# EasySerial.net
KiCad netlist of a schematic drawn in Altium Designer
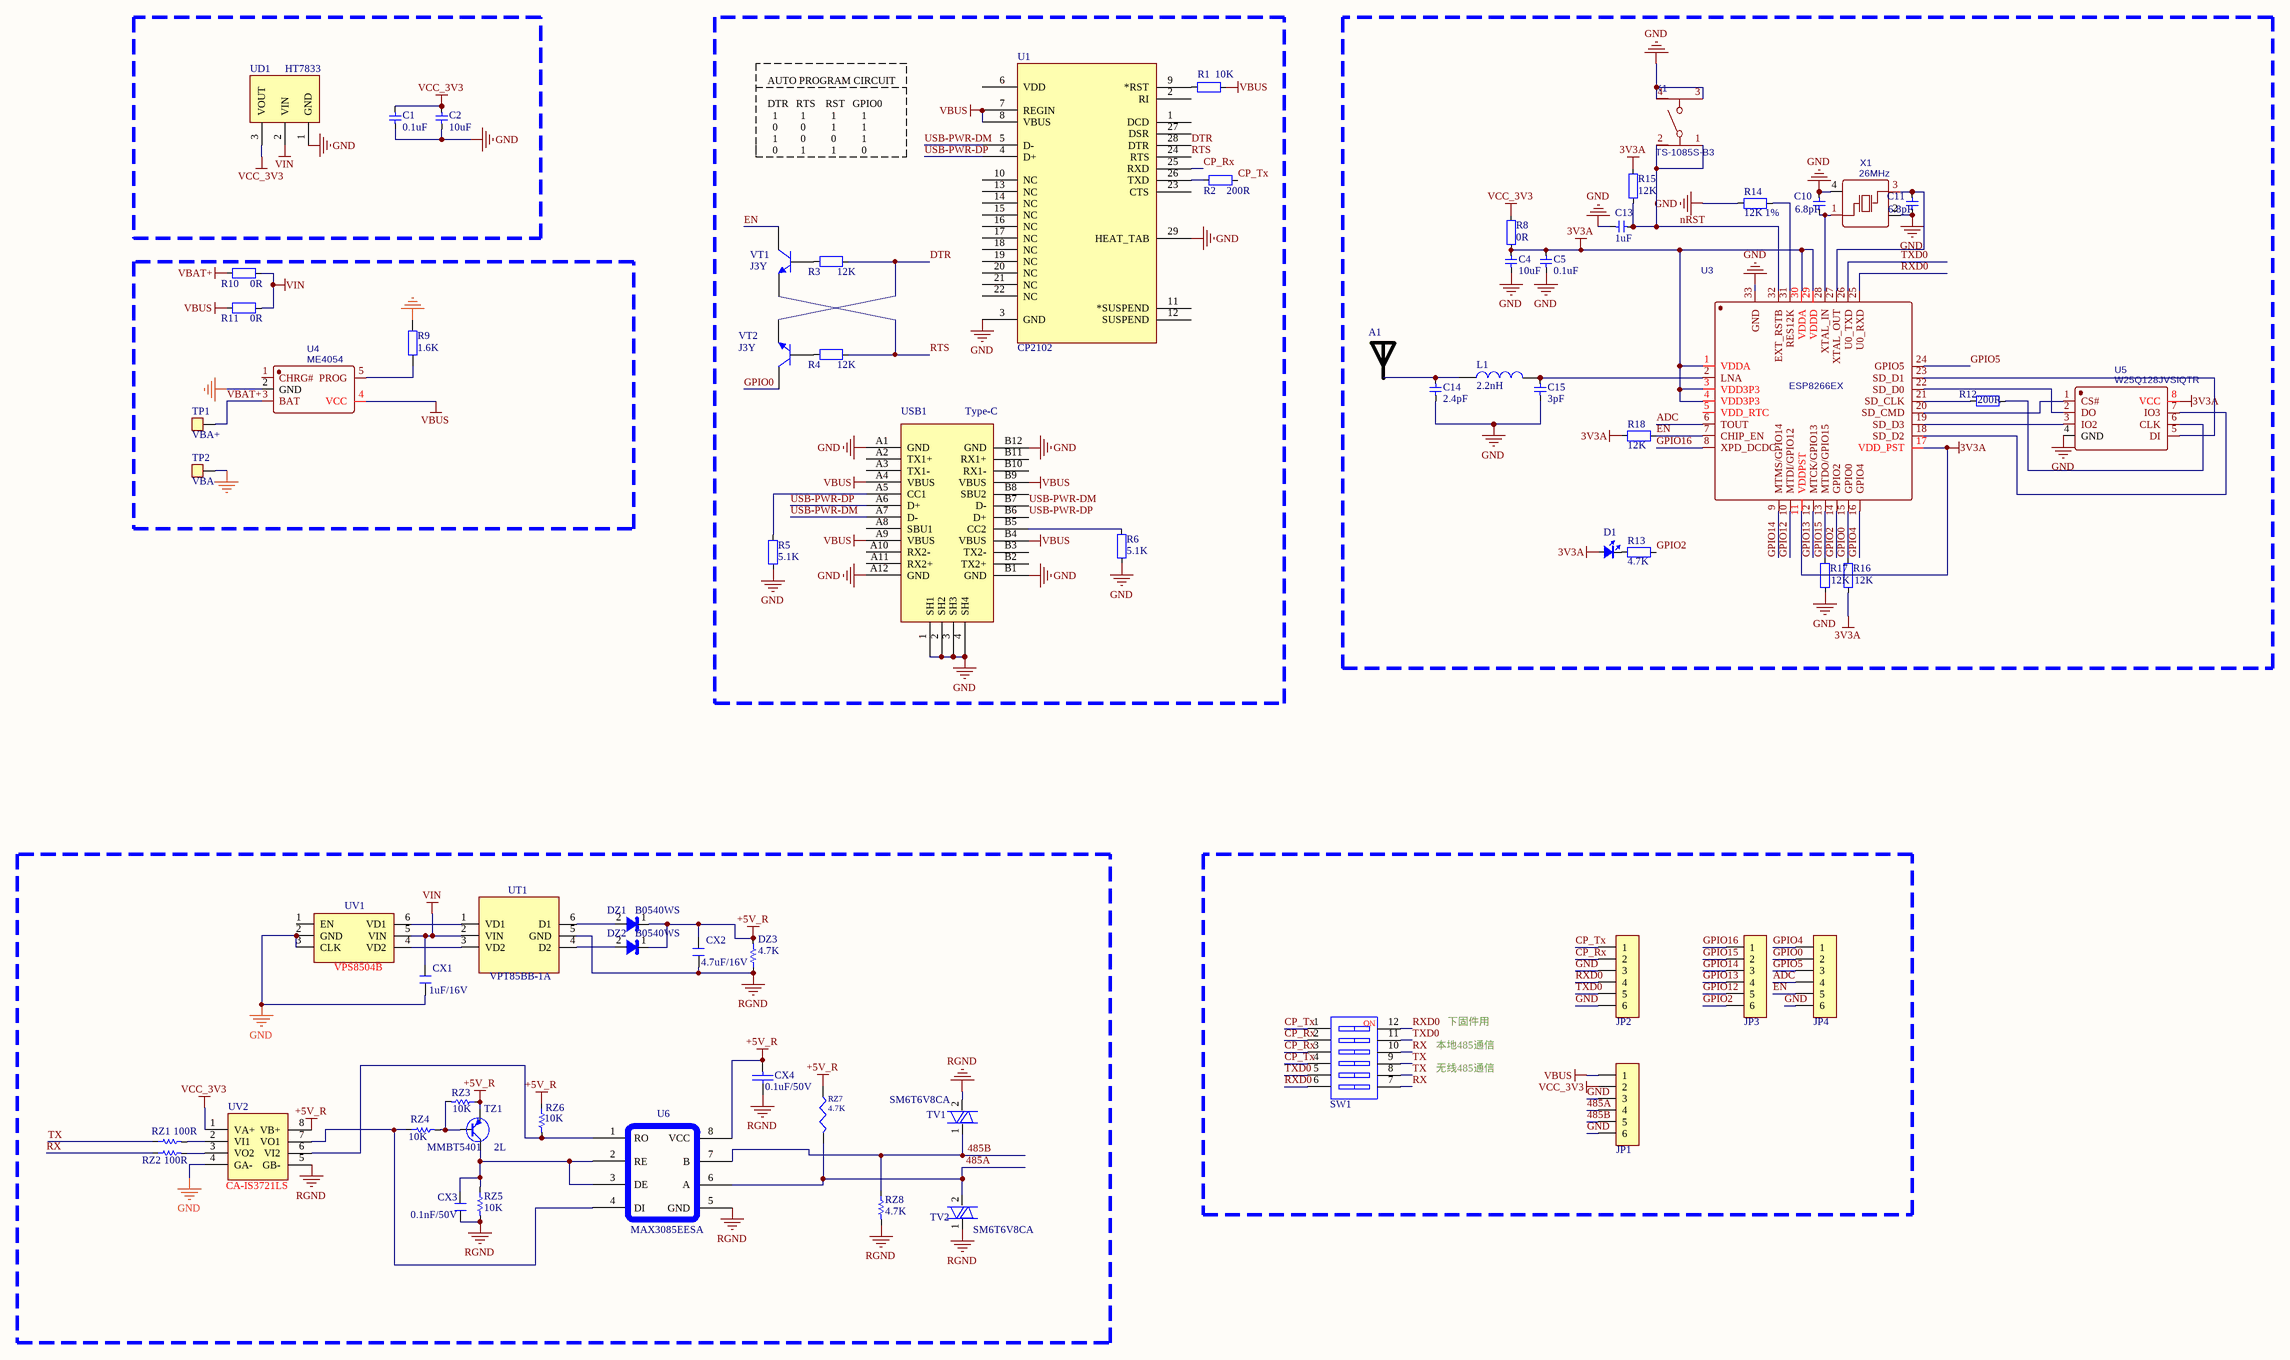
[diagram p0: EasySerial.SchDoc]

(export (version "E")
  (design (tool "Eeschema 10.0.6"))
  (components
    (comp (ref "A1")
      (value "RAINSUN")
      (footprint "ANT-Rainsun-AN5120")
      (libsource (lib "MyPcbLib") (part "ANT-Rainsun-AP5120"))
    )
    (comp (ref "C1")
      (value "0.1uF")
      (footprint "C 0402")
      (description "Capacitor")
      (libsource (lib "MyPcbLib") (part "电容-0402"))
    )
    (comp (ref "C2")
      (value "10uF")
      (footprint "C 0402")
      (description "Capacitor")
      (libsource (lib "MyPcbLib") (part "电容-0402"))
    )
    (comp (ref "C4")
      (value "10uF")
      (footprint "C 0402")
      (description "Capacitor")
      (libsource (lib "MyPcbLib") (part "电容-0402"))
    )
    (comp (ref "C5")
      (value "0.1uF")
      (footprint "C 0402")
      (description "Capacitor")
      (libsource (lib "MyPcbLib") (part "电容-0402"))
    )
    (comp (ref "C10")
      (value "6.8pF")
      (footprint "C 0402")
      (description "Capacitor")
      (libsource (lib "MyPcbLib") (part "电容-0402"))
    )
    (comp (ref "C11")
      (value "6.8pF")
      (footprint "C 0402")
      (description "Capacitor")
      (libsource (lib "MyPcbLib") (part "电容-0402"))
    )
    (comp (ref "C13")
      (value "1uF")
      (footprint "C 0402")
      (description "Capacitor")
      (libsource (lib "MyPcbLib") (part "电容-0402"))
    )
    (comp (ref "C14")
      (value "2.4pF")
      (footprint "C 0402")
      (description "Capacitor")
      (libsource (lib "MyPcbLib") (part "电容-0402"))
    )
    (comp (ref "C15")
      (value "3pF")
      (footprint "C 0402")
      (description "Capacitor")
      (libsource (lib "MyPcbLib") (part "电容-0402"))
    )
    (comp (ref "CX1") (value "1uF/16V") (footprint "C 0402") (libsource (lib "DaWei") (part "CAP")))
    (comp (ref "CX2") (value "4.7uF/16V") (footprint "C 0402") (libsource (lib "DaWei") (part "CAP")))
    (comp (ref "CX3") (value "0.1nF/50V") (footprint "C 0402") (libsource (lib "DaWei") (part "CAP")))
    (comp (ref "CX4")
      (value "0.1uF/50V")
      (footprint "C 0402")
      (description "Capacitor")
      (libsource (lib "*") (part "CAP"))
    )
    (comp (ref "D1")
      (value "color?")
      (footprint "LED_0402_RED")
      (description "LED")
      (libsource (lib "ESP32-PicoDK") (part "LED_0402"))
    )
    (comp (ref "DZ1") (value "B0540WS") (footprint "SOD-323F") (libsource (lib "DaWei") (part "DIODE")))
    (comp (ref "DZ2") (value "B0540WS") (footprint "SOD-323F") (libsource (lib "DaWei") (part "DIODE")))
    (comp (ref "DZ3") (value "4.7K") (footprint "R 0402") (libsource (lib "DaWei") (part "R-SMD")))
    (comp (ref "JP1")
      (value "HDR-1X6")
      (footprint "HDR2.54 S-W-6P")
      (description "6P接插件")
      (fields (field (name "版权归属") "源创客"))
      (libsource (lib "接插件") (part "Header 6"))
    )
    (comp (ref "JP2")
      (value "HDR-1X6")
      (footprint "HDR2.54 S-W-6P")
      (description "6P接插件")
      (fields (field (name "版权归属") "源创客"))
      (libsource (lib "接插件") (part "Header 6"))
    )
    (comp (ref "JP3")
      (value "HDR-1X6")
      (footprint "HDR-1X6")
      (description "6P接插件")
      (fields (field (name "版权归属") "源创客"))
      (libsource (lib "接插件") (part "Header 6"))
    )
    (comp (ref "JP4")
      (value "HDR-1X6")
      (footprint "HDR-1X6")
      (description "6P接插件")
      (fields (field (name "版权归属") "源创客"))
      (libsource (lib "接插件") (part "Header 6"))
    )
    (comp (ref "K1")
      (value "TS-1085S-B3")
      (footprint "TS-1085S-B3")
      (fields (field (name "BOM_SUPPLIER PART") "C498298") (field (name "CONTRIBUTOR") "LCSC"))
      (libsource (lib "altium-import") (part "root_2_TS-1085S-B3_"))
    )
    (comp (ref "L1")
      (value "2.2nH")
      (footprint "L 0402")
      (description "小功率贴片电感")
      (fields (field (name "版权归属") "源创客"))
      (libsource (lib "电阻-电容-电感") (part "L"))
    )
    (comp (ref "R1")
      (value "10K")
      (footprint "R 0402")
      (description "Resistor")
      (libsource (lib "") (part "电阻-0402_3"))
    )
    (comp (ref "R2")
      (value "200R")
      (footprint "R 0402")
      (description "Resistor")
      (libsource (lib "") (part "电阻-0402_3"))
    )
    (comp (ref "R3")
      (value "12K")
      (footprint "R 0402")
      (description "Resistor")
      (libsource (lib "") (part "电阻-0402_3"))
    )
    (comp (ref "R4")
      (value "12K")
      (footprint "R 0402")
      (description "Resistor")
      (libsource (lib "") (part "电阻-0402_3"))
    )
    (comp (ref "R5")
      (value "5.1K")
      (footprint "R 0402")
      (description "Resistor")
      (libsource (lib "") (part "电阻-0402_1"))
    )
    (comp (ref "R6")
      (value "5.1K")
      (footprint "R 0402")
      (description "Resistor")
      (libsource (lib "") (part "电阻-0402_1"))
    )
    (comp (ref "R8")
      (value "0R")
      (footprint "R 0402")
      (description "Resistor")
      (libsource (lib "") (part "电阻-0402_1"))
    )
    (comp (ref "R9")
      (value "1.6K")
      (footprint "R 0603")
      (description "Resistor")
      (fields (field (name "PUBLISHER") "Altium Limited"))
      (libsource (lib "Miscellaneous Devices") (part "Res2"))
    )
    (comp (ref "R10")
      (value "0R")
      (footprint "R 0603")
      (description "Resistor")
      (libsource (lib "") (part "电阻-0402_3"))
    )
    (comp (ref "R11")
      (value "0R")
      (footprint "R 0603")
      (description "Resistor")
      (libsource (lib "") (part "电阻-0402_3"))
    )
    (comp (ref "R12")
      (value "200R")
      (footprint "R 0402")
      (description "Resistor")
      (libsource (lib "") (part "电阻-0402_2"))
    )
    (comp (ref "R13")
      (value "4.7K")
      (footprint "R 0402")
      (description "Resistor")
      (libsource (lib "") (part "电阻-0402_2"))
    )
    (comp (ref "R14")
      (value "12K 1%")
      (footprint "R 0402")
      (description "Resistor")
      (libsource (lib "") (part "电阻-0402_2"))
    )
    (comp (ref "R15")
      (value "12K")
      (footprint "R 0402")
      (description "Resistor")
      (libsource (lib "MyPcbLib") (part "电阻-0402"))
    )
    (comp (ref "R16")
      (value "12K")
      (footprint "R 0402")
      (description "Resistor")
      (libsource (lib "MyPcbLib") (part "电阻-0402"))
    )
    (comp (ref "R17")
      (value "12K")
      (footprint "R 0402")
      (description "Resistor")
      (libsource (lib "MyPcbLib") (part "电阻-0402"))
    )
    (comp (ref "R18")
      (value "12K")
      (footprint "R 0402")
      (description "Resistor")
      (libsource (lib "") (part "电阻-0402_3"))
    )
    (comp (ref "RZ1") (value "100R") (footprint "R 0402") (libsource (lib "DaWei") (part "R-SMD")))
    (comp (ref "RZ2") (value "100R") (footprint "R 0402") (libsource (lib "DaWei") (part "R-SMD")))
    (comp (ref "RZ3") (value "10K") (footprint "R 0402") (libsource (lib "DaWei") (part "R-SMD")))
    (comp (ref "RZ4") (value "10K") (footprint "R 0402") (libsource (lib "DaWei") (part "R-SMD")))
    (comp (ref "RZ5") (value "10K") (footprint "R 0402") (libsource (lib "DaWei") (part "R-SMD")))
    (comp (ref "RZ6") (value "10K") (footprint "R 0402") (libsource (lib "DaWei") (part "R-SMD")))
    (comp (ref "RZ7") (value "4.7K") (footprint "R 0402") (libsource (lib "*") (part "RES1")))
    (comp (ref "RZ8") (value "4.7K") (footprint "R 0402") (libsource (lib "DaWei") (part "R-SMD")))
    (comp (ref "SW1")
      (value "CSW-6P")
      (footprint "CSW1.27 SMD-6P")
      (description "6路编码开关")
      (fields (field (name "版权归属") "源创客"))
      (libsource (lib "按键-开关") (part "CSW-6P"))
    )
    (comp (ref "TP1")
      (value "VBA+")
      (footprint "TEST 1.8")
      (description "测试点")
      (fields (field (name "版权归属") "源创客"))
      (libsource (lib "未分类器件") (part "TEST_D"))
    )
    (comp (ref "TP2")
      (value "VBA-")
      (footprint "TEST 1.8")
      (description "测试点")
      (fields (field (name "版权归属") "源创客"))
      (libsource (lib "未分类器件") (part "TEST_D"))
    )
    (comp (ref "TV1") (value "SM6T6V8CA") (footprint "SMB") (libsource (lib "*") (part "ZD1")))
    (comp (ref "TV2") (value "SM6T6V8CA") (footprint "SMB") (libsource (lib "*") (part "ZD1")))
    (comp (ref "TZ1")
      (value "MMBT5401     2L")
      (footprint "SOT23-3N")
      (libsource (lib "DaWei") (part "PNP_R"))
    )
    (comp (ref "U1")
      (value "CP2102")
      (footprint "QFN-28")
      (description "USB转TTL")
      (libsource (lib "mLib") (part "CP2102"))
    )
    (comp (ref "U3")
      (value "ESP8266EX")
      (footprint "QFN32 5x5_L")
      (fields (field (name "BOM_SUPPLIER PART") "C77967"))
      (libsource (lib "altium-import") (part "root_0_ESP8266EX_"))
    )
    (comp (ref "U4")
      (value "ME4054")
      (footprint "SOT23-5L")
      (fields
        (field (name "BOM_SUPPLIER PART") "C521413")
        (field (name "BOM_MANUFACTURER PART") "SD8054")
        (field (name "CONTRIBUTOR") "LCSC")
      )
      (libsource (lib "altium-import") (part "root_0_SD8054_"))
    )
    (comp (ref "U5")
      (value "W25Q128JVSIQTR")
      (footprint "SOP8W_L")
      (fields (field (name "BOM_SUPPLIER PART") "C97521"))
      (libsource (lib "altium-import") (part "root_0_W25Q128JVSIQTR_"))
    )
    (comp (ref "U6") (value "MAX3085EESA") (footprint "SOP8_M") (libsource (lib "*") (part "MAX485")))
    (comp (ref "UD1")
      (value "HT7833")
      (footprint "SOT89_N")
      (description "LDO")
      (libsource (lib "DaWei") (part "HT75XX"))
    )
    (comp (ref "USB1")
      (value "Type-C")
      (footprint "Type-C")
      (libsource (lib "MyPcbLib") (part "USB-Type-C-TOP"))
    )
    (comp (ref "UT1")
      (value "VPT85BB-1A")
      (footprint "VPT85BB-1A")
      (description "源特推挽变压器")
      (libsource (lib "DaWei") (part "T-SMD"))
    )
    (comp (ref "UV1")
      (value "VPS8504B")
      (footprint "SOT23-6N")
      (description "源特微功率隔离电源专用芯片")
      (libsource (lib "DaWei") (part "VPS8504"))
    )
    (comp (ref "UV2")
      (value "CA-IS3721LS")
      (footprint "SOP8_N")
      (description "上海川土微电子隔离数字芯片")
      (libsource (lib "DaWei") (part "CA-IS3721LS"))
    )
    (comp (ref "VT1")
      (value "J3Y")
      (footprint "SOT23-3N")
      (description "Surface mount NPN transistor, package SOT-23")
      (libsource (lib "MyPcbLib") (part "SMT_TRIODE_NPN"))
    )
    (comp (ref "VT2")
      (value "J3Y")
      (footprint "SOT23-3N")
      (description "Surface mount NPN transistor, package SOT-23")
      (libsource (lib "MyPcbLib") (part "SMT_TRIODE_NPN"))
    )
    (comp (ref "X1")
      (value "26MHz")
      (footprint "XTAL-2520")
      (fields
        (field (name "BOM_MANUFACTURER PART") "NX3225SA-30M")
        (field (name "BOM_SUPPLIER PART") "C139739")
        (field (name "CONTRIBUTOR") "LCSC")
      )
      (libsource (lib "altium-import") (part "root_0_30MHz_"))
    )
  )
  (nets
    (net (code "1") (name "+5V_R") (class "Default")
      (node (ref "CX2") (pin "1") (pinfunction "1_1") (pintype "passive"))
      (node (ref "CX4") (pin "1") (pinfunction "1_1") (pintype "passive"))
      (node (ref "DZ1") (pin "1") (pintype "passive"))
      (node (ref "DZ2") (pin "1") (pintype "passive"))
      (node (ref "DZ3") (pin "2") (pinfunction "2_2") (pintype "passive"))
      (node (ref "RZ3") (pin "1") (pinfunction "1_1") (pintype "passive"))
      (node (ref "RZ6") (pin "1") (pinfunction "1_1") (pintype "passive"))
      (node (ref "RZ7") (pin "1") (pinfunction "1_1") (pintype "passive"))
      (node (ref "TZ1") (pin "2") (pintype "passive"))
      (node (ref "U6") (pin "8") (pinfunction "VCC_8") (pintype "passive"))
      (node (ref "UV2") (pin "8") (pinfunction "VB+_8") (pintype "passive"))
    )
    (net (code "2") (name "/485A") (class "Default")
      (node (ref "JP1") (pin "4") (pinfunction "4_4") (pintype "passive"))
      (node (ref "RZ7") (pin "2") (pinfunction "2_2") (pintype "passive"))
      (node (ref "TV2") (pin "2") (pintype "passive"))
      (node (ref "U6") (pin "6") (pinfunction "A_6") (pintype "passive"))
    )
    (net (code "3") (name "/485B") (class "Default")
      (node (ref "JP1") (pin "5") (pinfunction "5_5") (pintype "passive"))
      (node (ref "RZ8") (pin "1") (pinfunction "1_1") (pintype "passive"))
      (node (ref "TV1") (pin "1") (pintype "passive"))
      (node (ref "U6") (pin "7") (pinfunction "B_7") (pintype "passive"))
    )
    (net (code "4") (name "/ADC") (class "Default")
      (node (ref "JP4") (pin "4") (pinfunction "4_4") (pintype "passive"))
      (node (ref "U3") (pin "6") (pinfunction "TOUT_6") (pintype "passive"))
    )
    (net (code "5") (name "/CP_Rx") (class "Default")
      (node (ref "JP2") (pin "2") (pinfunction "2_2") (pintype "passive"))
      (node (ref "SW1") (pin "2") (pinfunction "2_2") (pintype "passive"))
      (node (ref "SW1") (pin "3") (pinfunction "3_3") (pintype "passive"))
      (node (ref "U1") (pin "25") (pinfunction "RXD_25") (pintype "passive"))
    )
    (net (code "6") (name "/CP_Tx") (class "Default")
      (node (ref "JP2") (pin "1") (pinfunction "1_1") (pintype "passive"))
      (node (ref "R2") (pin "1") (pinfunction "1_1") (pintype "passive"))
      (node (ref "SW1") (pin "1") (pinfunction "1_1") (pintype "passive"))
      (node (ref "SW1") (pin "4") (pinfunction "4_4") (pintype "passive"))
    )
    (net (code "7") (name "/DTR") (class "Default")
      (node (ref "R3") (pin "1") (pinfunction "1_1") (pintype "passive"))
      (node (ref "U1") (pin "28") (pinfunction "DTR_28") (pintype "passive"))
      (node (ref "VT2") (pin "2") (pinfunction "E_2") (pintype "passive"))
    )
    (net (code "8") (name "/EN") (class "Default")
      (node (ref "JP4") (pin "5") (pinfunction "5_5") (pintype "passive"))
      (node (ref "R18") (pin "1") (pinfunction "1_1") (pintype "passive"))
      (node (ref "U3") (pin "7") (pinfunction "CHIP_EN_7") (pintype "passive"))
      (node (ref "VT1") (pin "3") (pinfunction "C_3") (pintype "passive"))
    )
    (net (code "9") (name "/GPIO0") (class "Default")
      (node (ref "JP4") (pin "2") (pinfunction "2_2") (pintype "passive"))
      (node (ref "R16") (pin "2") (pinfunction "2_2") (pintype "passive"))
      (node (ref "U3") (pin "15") (pinfunction "GPIO0_15") (pintype "passive"))
      (node (ref "VT2") (pin "3") (pinfunction "C_3") (pintype "passive"))
    )
    (net (code "10") (name "/GPIO2") (class "Default")
      (node (ref "JP3") (pin "6") (pinfunction "6_6") (pintype "passive"))
      (node (ref "R13") (pin "2") (pinfunction "2_2") (pintype "passive"))
      (node (ref "U3") (pin "14") (pinfunction "GPIO2_14") (pintype "passive"))
    )
    (net (code "11") (name "/GPIO4") (class "Default")
      (node (ref "JP4") (pin "1") (pinfunction "1_1") (pintype "passive"))
      (node (ref "U3") (pin "16") (pinfunction "GPIO4_16") (pintype "passive"))
    )
    (net (code "12") (name "/GPIO5") (class "Default")
      (node (ref "JP4") (pin "3") (pinfunction "3_3") (pintype "passive"))
      (node (ref "U3") (pin "24") (pinfunction "GPIO5_24") (pintype "passive"))
    )
    (net (code "13") (name "/GPIO12") (class "Default")
      (node (ref "JP3") (pin "5") (pinfunction "5_5") (pintype "passive"))
      (node (ref "U3") (pin "10") (pinfunction "MTDI/GPIO12_10") (pintype "passive"))
    )
    (net (code "14") (name "/GPIO13") (class "Default")
      (node (ref "JP3") (pin "4") (pinfunction "4_4") (pintype "passive"))
      (node (ref "U3") (pin "12") (pinfunction "MTCK/GPIO13_12") (pintype "passive"))
    )
    (net (code "15") (name "/GPIO14") (class "Default")
      (node (ref "JP3") (pin "3") (pinfunction "3_3") (pintype "passive"))
      (node (ref "U3") (pin "9") (pinfunction "MTMS/GPIO14_9") (pintype "passive"))
    )
    (net (code "16") (name "/GPIO15") (class "Default")
      (node (ref "JP3") (pin "2") (pinfunction "2_2") (pintype "passive"))
      (node (ref "R17") (pin "2") (pinfunction "2_2") (pintype "passive"))
      (node (ref "U3") (pin "13") (pinfunction "MTDO/GPIO15_13") (pintype "passive"))
    )
    (net (code "17") (name "/GPIO16") (class "Default")
      (node (ref "JP3") (pin "1") (pinfunction "1_1") (pintype "passive"))
      (node (ref "U3") (pin "8") (pinfunction "XPD_DCDC_8") (pintype "passive"))
    )
    (net (code "18") (name "/RTS") (class "Default")
      (node (ref "R4") (pin "1") (pinfunction "1_1") (pintype "passive"))
      (node (ref "U1") (pin "24") (pinfunction "RTS_24") (pintype "passive"))
      (node (ref "VT1") (pin "2") (pinfunction "E_2") (pintype "passive"))
    )
    (net (code "19") (name "/RX") (class "Default")
      (node (ref "RZ2") (pin "1") (pinfunction "1_1") (pintype "passive"))
      (node (ref "SW1") (pin "10") (pinfunction "10_10") (pintype "passive"))
      (node (ref "SW1") (pin "7") (pinfunction "7_7") (pintype "passive"))
    )
    (net (code "20") (name "/RXD0") (class "Default")
      (node (ref "JP2") (pin "4") (pinfunction "4_4") (pintype "passive"))
      (node (ref "SW1") (pin "12") (pinfunction "12_12") (pintype "passive"))
      (node (ref "SW1") (pin "6") (pinfunction "6_6") (pintype "passive"))
      (node (ref "U3") (pin "25") (pinfunction "U0_RXD_25") (pintype "passive"))
    )
    (net (code "21") (name "/TX") (class "Default")
      (node (ref "RZ1") (pin "1") (pinfunction "1_1") (pintype "passive"))
      (node (ref "SW1") (pin "8") (pinfunction "8_8") (pintype "passive"))
      (node (ref "SW1") (pin "9") (pinfunction "9_9") (pintype "passive"))
    )
    (net (code "22") (name "/TXD0") (class "Default")
      (node (ref "JP2") (pin "5") (pinfunction "5_5") (pintype "passive"))
      (node (ref "SW1") (pin "11") (pinfunction "11_11") (pintype "passive"))
      (node (ref "SW1") (pin "5") (pinfunction "5_5") (pintype "passive"))
      (node (ref "U3") (pin "26") (pinfunction "U0_TXD_26") (pintype "passive"))
    )
    (net (code "23") (name "/USB-PWR-DM") (class "Default")
      (node (ref "U1") (pin "5") (pinfunction "D-_5") (pintype "passive"))
      (node (ref "USB1") (pin "A7") (pinfunction "D-_A7") (pintype "passive"))
      (node (ref "USB1") (pin "B7") (pinfunction "D-_B7") (pintype "passive"))
    )
    (net (code "24") (name "/USB-PWR-DP") (class "Default")
      (node (ref "U1") (pin "4") (pinfunction "D+_4") (pintype "passive"))
      (node (ref "USB1") (pin "A6") (pinfunction "D+_A6") (pintype "passive"))
      (node (ref "USB1") (pin "B6") (pinfunction "D+_B6") (pintype "passive"))
    )
    (net (code "25") (name "/nRST") (class "Default")
      (node (ref "C13") (pin "1") (pinfunction "1_1") (pintype "passive"))
      (node (ref "K1") (pin "1") (pinfunction "1_1") (pintype "passive"))
      (node (ref "K1") (pin "2") (pinfunction "2_2") (pintype "passive"))
      (node (ref "R15") (pin "1") (pinfunction "1_1") (pintype "passive"))
      (node (ref "U3") (pin "32") (pinfunction "EXT_RSTB_32") (pintype "passive"))
    )
    (net (code "26") (name "3V3A") (class "Default")
      (node (ref "C4") (pin "2") (pinfunction "2_2") (pintype "passive"))
      (node (ref "C5") (pin "2") (pinfunction "2_2") (pintype "passive"))
      (node (ref "D1") (pin "1") (pinfunction "A_1") (pintype "passive"))
      (node (ref "R15") (pin "2") (pinfunction "2_2") (pintype "passive"))
      (node (ref "R16") (pin "1") (pinfunction "1_1") (pintype "passive"))
      (node (ref "R18") (pin "2") (pinfunction "2_2") (pintype "passive"))
      (node (ref "R8") (pin "2") (pinfunction "2_2") (pintype "passive"))
      (node (ref "U3") (pin "1") (pinfunction "VDDA_1") (pintype "passive"))
      (node (ref "U3") (pin "11") (pinfunction "VDDPST_11") (pintype "passive"))
      (node (ref "U3") (pin "17") (pinfunction "VDD_PST_17") (pintype "passive"))
      (node (ref "U3") (pin "29") (pinfunction "VDDD_29") (pintype "passive"))
      (node (ref "U3") (pin "3") (pinfunction "VDD3P3_3") (pintype "passive"))
      (node (ref "U3") (pin "30") (pinfunction "VDDA_30") (pintype "passive"))
      (node (ref "U3") (pin "4") (pinfunction "VDD3P3_4") (pintype "passive"))
      (node (ref "U5") (pin "8") (pinfunction "VCC_8") (pintype "passive"))
    )
    (net (code "27") (name "GND") (class "Default")
      (node (ref "C1") (pin "1") (pinfunction "1_1") (pintype "passive"))
      (node (ref "C10") (pin "2") (pinfunction "2_2") (pintype "passive"))
      (node (ref "C11") (pin "1") (pinfunction "1_1") (pintype "passive"))
      (node (ref "C13") (pin "2") (pinfunction "2_2") (pintype "passive"))
      (node (ref "C14") (pin "1") (pinfunction "1_1") (pintype "passive"))
      (node (ref "C15") (pin "1") (pinfunction "1_1") (pintype "passive"))
      (node (ref "C2") (pin "1") (pinfunction "1_1") (pintype "passive"))
      (node (ref "C4") (pin "1") (pinfunction "1_1") (pintype "passive"))
      (node (ref "C5") (pin "1") (pinfunction "1_1") (pintype "passive"))
      (node (ref "CX1") (pin "2") (pinfunction "2_2") (pintype "passive"))
      (node (ref "JP1") (pin "3") (pinfunction "3_3") (pintype "passive"))
      (node (ref "JP1") (pin "6") (pinfunction "6_6") (pintype "passive"))
      (node (ref "JP2") (pin "3") (pinfunction "3_3") (pintype "passive"))
      (node (ref "JP2") (pin "6") (pinfunction "6_6") (pintype "passive"))
      (node (ref "JP4") (pin "6") (pinfunction "6_6") (pintype "passive"))
      (node (ref "K1") (pin "3") (pinfunction "3_3") (pintype "passive"))
      (node (ref "K1") (pin "4") (pinfunction "4_4") (pintype "passive"))
      (node (ref "R14") (pin "1") (pinfunction "1_1") (pintype "passive"))
      (node (ref "R17") (pin "1") (pinfunction "1_1") (pintype "passive"))
      (node (ref "R5") (pin "2") (pinfunction "2_2") (pintype "passive"))
      (node (ref "R6") (pin "2") (pinfunction "2_2") (pintype "passive"))
      (node (ref "R9") (pin "1") (pinfunction "1_1") (pintype "passive"))
      (node (ref "TP2") (pin "1") (pinfunction "1_1") (pintype "passive"))
      (node (ref "U1") (pin "29") (pinfunction "HEAT_TAB_29") (pintype "passive"))
      (node (ref "U1") (pin "3") (pinfunction "GND_3") (pintype "passive"))
      (node (ref "U3") (pin "33") (pinfunction "GND_33") (pintype "passive"))
      (node (ref "U4") (pin "2") (pinfunction "GND_2") (pintype "passive"))
      (node (ref "U5") (pin "4") (pinfunction "GND_4") (pintype "passive"))
      (node (ref "UD1") (pin "1") (pinfunction "GND_1") (pintype "passive"))
      (node (ref "USB1") (pin "1") (pinfunction "SH1_1") (pintype "passive"))
      (node (ref "USB1") (pin "2") (pinfunction "SH2_2") (pintype "passive"))
      (node (ref "USB1") (pin "3") (pinfunction "SH3_3") (pintype "passive"))
      (node (ref "USB1") (pin "4") (pinfunction "SH4_4") (pintype "passive"))
      (node (ref "USB1") (pin "A1") (pinfunction "GND_A1") (pintype "passive"))
      (node (ref "USB1") (pin "A12") (pinfunction "GND_A12") (pintype "passive"))
      (node (ref "USB1") (pin "B1") (pinfunction "GND_B1") (pintype "passive"))
      (node (ref "USB1") (pin "B12") (pinfunction "GND_B12") (pintype "passive"))
      (node (ref "UV1") (pin "2") (pinfunction "GND_2") (pintype "passive"))
      (node (ref "UV1") (pin "3") (pinfunction "CLK_3") (pintype "passive"))
      (node (ref "UV2") (pin "4") (pinfunction "GA-_4") (pintype "passive"))
      (node (ref "X1") (pin "2") (pinfunction "GND_2") (pintype "passive"))
      (node (ref "X1") (pin "4") (pinfunction "GND_4") (pintype "passive"))
    )
    (net (code "28") (name "Net-(A1-Pad1)") (class "Default")
      (node (ref "A1") (pin "1") (pinfunction "1_1") (pintype "passive"))
      (node (ref "C14") (pin "2") (pinfunction "2_2") (pintype "passive"))
      (node (ref "L1") (pin "1") (pinfunction "1_1") (pintype "passive"))
    )
    (net (code "29") (name "Net-(D1-K)") (class "Default")
      (node (ref "D1") (pin "2") (pinfunction "K_2") (pintype "passive"))
      (node (ref "R13") (pin "1") (pinfunction "1_1") (pintype "passive"))
    )
    (net (code "30") (name "Net-(RZ3-Pad2)") (class "Default")
      (node (ref "RZ3") (pin "2") (pinfunction "2_2") (pintype "passive"))
      (node (ref "RZ4") (pin "2") (pinfunction "2_2") (pintype "passive"))
      (node (ref "TZ1") (pin "1") (pintype "passive"))
    )
    (net (code "31") (name "Net-(U1-*RST)") (class "Default")
      (node (ref "R1") (pin "2") (pinfunction "2_2") (pintype "passive"))
      (node (ref "U1") (pin "9") (pinfunction "*RST_9") (pintype "passive"))
    )
    (net (code "32") (name "Net-(U1-TXD)") (class "Default")
      (node (ref "R2") (pin "2") (pinfunction "2_2") (pintype "passive"))
      (node (ref "U1") (pin "26") (pinfunction "TXD_26") (pintype "passive"))
    )
    (net (code "33") (name "Net-(U3-LNA)") (class "Default")
      (node (ref "C15") (pin "2") (pinfunction "2_2") (pintype "passive"))
      (node (ref "L1") (pin "2") (pinfunction "2_2") (pintype "passive"))
      (node (ref "U3") (pin "2") (pinfunction "LNA_2") (pintype "passive"))
    )
    (net (code "34") (name "Net-(U3-RES12K)") (class "Default")
      (node (ref "R14") (pin "2") (pinfunction "2_2") (pintype "passive"))
      (node (ref "U3") (pin "31") (pinfunction "RES12K_31") (pintype "passive"))
    )
    (net (code "35") (name "Net-(U3-SD_CLK)") (class "Default")
      (node (ref "R12") (pin "1") (pinfunction "1_1") (pintype "passive"))
      (node (ref "U3") (pin "21") (pinfunction "SD_CLK_21") (pintype "passive"))
    )
    (net (code "36") (name "Net-(U3-SD_CMD)") (class "Default")
      (node (ref "U3") (pin "20") (pinfunction "SD_CMD_20") (pintype "passive"))
      (node (ref "U5") (pin "1") (pinfunction "CS#_1") (pintype "passive"))
    )
    (net (code "37") (name "Net-(U3-SD_D0)") (class "Default")
      (node (ref "U3") (pin "22") (pinfunction "SD_D0_22") (pintype "passive"))
      (node (ref "U5") (pin "2") (pinfunction "DO_2") (pintype "passive"))
    )
    (net (code "38") (name "Net-(U3-SD_D1)") (class "Default")
      (node (ref "U3") (pin "23") (pinfunction "SD_D1_23") (pintype "passive"))
      (node (ref "U5") (pin "5") (pinfunction "DI_5") (pintype "passive"))
    )
    (net (code "39") (name "Net-(U3-SD_D2)") (class "Default")
      (node (ref "U3") (pin "18") (pinfunction "SD_D2_18") (pintype "passive"))
      (node (ref "U5") (pin "7") (pinfunction "IO3_7") (pintype "passive"))
    )
    (net (code "40") (name "Net-(U3-SD_D3)") (class "Default")
      (node (ref "U3") (pin "19") (pinfunction "SD_D3_19") (pintype "passive"))
      (node (ref "U5") (pin "3") (pinfunction "IO2_3") (pintype "passive"))
    )
    (net (code "41") (name "Net-(U3-XTAL_IN)") (class "Default")
      (node (ref "C10") (pin "1") (pinfunction "1_1") (pintype "passive"))
      (node (ref "U3") (pin "28") (pinfunction "XTAL_IN_28") (pintype "passive"))
      (node (ref "X1") (pin "1") (pinfunction "OSC1_1") (pintype "passive"))
    )
    (net (code "42") (name "Net-(U3-XTAL_OUT)") (class "Default")
      (node (ref "C11") (pin "2") (pinfunction "2_2") (pintype "passive"))
      (node (ref "U3") (pin "27") (pinfunction "XTAL_OUT_27") (pintype "passive"))
      (node (ref "X1") (pin "3") (pinfunction "OSC2_3") (pintype "passive"))
    )
    (net (code "43") (name "Net-(U4-PROG)") (class "Default")
      (node (ref "R9") (pin "2") (pinfunction "2_2") (pintype "passive"))
      (node (ref "U4") (pin "5") (pinfunction "PROG_5") (pintype "passive"))
    )
    (net (code "44") (name "Net-(U5-CLK)") (class "Default")
      (node (ref "R12") (pin "2") (pinfunction "2_2") (pintype "passive"))
      (node (ref "U5") (pin "6") (pinfunction "CLK_6") (pintype "passive"))
    )
    (net (code "45") (name "Net-(U6-DE)") (class "Default")
      (node (ref "CX3") (pin "2") (pinfunction "2_2") (pintype "passive"))
      (node (ref "RZ5") (pin "1") (pinfunction "1_1") (pintype "passive"))
      (node (ref "TZ1") (pin "3") (pintype "passive"))
      (node (ref "U6") (pin "2") (pinfunction "RE_2") (pintype "passive"))
      (node (ref "U6") (pin "3") (pinfunction "DE_3") (pintype "passive"))
    )
    (net (code "46") (name "Net-(U6-DI)") (class "Default")
      (node (ref "RZ4") (pin "1") (pinfunction "1_1") (pintype "passive"))
      (node (ref "U6") (pin "4") (pinfunction "DI_4") (pintype "passive"))
      (node (ref "UV2") (pin "7") (pinfunction "VO1_7") (pintype "passive"))
    )
    (net (code "47") (name "Net-(U6-RO)") (class "Default")
      (node (ref "RZ6") (pin "2") (pinfunction "2_2") (pintype "passive"))
      (node (ref "U6") (pin "1") (pinfunction "RO_1") (pintype "passive"))
      (node (ref "UV2") (pin "6") (pinfunction "VI2_6") (pintype "passive"))
    )
    (net (code "48") (name "Net-(USB1-CC1)") (class "Default")
      (node (ref "R5") (pin "1") (pinfunction "1_1") (pintype "passive"))
      (node (ref "USB1") (pin "A5") (pinfunction "CC1_A5") (pintype "passive"))
    )
    (net (code "49") (name "Net-(USB1-CC2)") (class "Default")
      (node (ref "R6") (pin "1") (pinfunction "1_1") (pintype "passive"))
      (node (ref "USB1") (pin "B5") (pinfunction "CC2_B5") (pintype "passive"))
    )
    (net (code "50") (name "Net-(UT1-D1)") (class "Default")
      (node (ref "DZ1") (pin "2") (pintype "passive"))
      (node (ref "UT1") (pin "6") (pinfunction "D1_6") (pintype "passive"))
    )
    (net (code "51") (name "Net-(UT1-D2)") (class "Default")
      (node (ref "DZ2") (pin "2") (pintype "passive"))
      (node (ref "UT1") (pin "4") (pinfunction "D2_4") (pintype "passive"))
    )
    (net (code "52") (name "Net-(UT1-VD1)") (class "Default")
      (node (ref "UT1") (pin "1") (pinfunction "VD1_1") (pintype "passive"))
      (node (ref "UV1") (pin "6") (pinfunction "VD1_6") (pintype "passive"))
    )
    (net (code "53") (name "Net-(UT1-VD2)") (class "Default")
      (node (ref "UT1") (pin "3") (pinfunction "VD2_3") (pintype "passive"))
      (node (ref "UV1") (pin "4") (pinfunction "VD2_4") (pintype "passive"))
    )
    (net (code "54") (name "Net-(UV2-VI1)") (class "Default")
      (node (ref "RZ1") (pin "2") (pinfunction "2_2") (pintype "passive"))
      (node (ref "UV2") (pin "2") (pinfunction "VI1_2") (pintype "passive"))
    )
    (net (code "55") (name "Net-(UV2-VO2)") (class "Default")
      (node (ref "RZ2") (pin "2") (pinfunction "2_2") (pintype "passive"))
      (node (ref "UV2") (pin "3") (pinfunction "VO2_3") (pintype "passive"))
    )
    (net (code "56") (name "Net-(VT1-B)") (class "Default")
      (node (ref "R3") (pin "2") (pinfunction "2_2") (pintype "passive"))
      (node (ref "VT1") (pin "1") (pinfunction "B_1") (pintype "passive"))
    )
    (net (code "57") (name "Net-(VT2-B)") (class "Default")
      (node (ref "R4") (pin "2") (pinfunction "2_2") (pintype "passive"))
      (node (ref "VT2") (pin "1") (pinfunction "B_1") (pintype "passive"))
    )
    (net (code "58") (name "RGND") (class "Default")
      (node (ref "CX2") (pin "2") (pinfunction "2_2") (pintype "passive"))
      (node (ref "CX3") (pin "1") (pinfunction "1_1") (pintype "passive"))
      (node (ref "CX4") (pin "2") (pinfunction "2_2") (pintype "passive"))
      (node (ref "DZ3") (pin "1") (pinfunction "1_1") (pintype "passive"))
      (node (ref "RZ5") (pin "2") (pinfunction "2_2") (pintype "passive"))
      (node (ref "RZ8") (pin "2") (pinfunction "2_2") (pintype "passive"))
      (node (ref "TV1") (pin "2") (pintype "passive"))
      (node (ref "TV2") (pin "1") (pintype "passive"))
      (node (ref "U6") (pin "5") (pinfunction "GND_5") (pintype "passive"))
      (node (ref "UT1") (pin "5") (pinfunction "GND_5") (pintype "passive"))
      (node (ref "UV2") (pin "5") (pinfunction "GB-_5") (pintype "passive"))
    )
    (net (code "59") (name "VBAT+") (class "Default")
      (node (ref "R10") (pin "2") (pinfunction "2_2") (pintype "passive"))
      (node (ref "TP1") (pin "1") (pinfunction "1_1") (pintype "passive"))
      (node (ref "U4") (pin "3") (pinfunction "BAT_3") (pintype "passive"))
    )
    (net (code "60") (name "VBUS") (class "Default")
      (node (ref "JP1") (pin "1") (pinfunction "1_1") (pintype "passive"))
      (node (ref "R1") (pin "1") (pinfunction "1_1") (pintype "passive"))
      (node (ref "R11") (pin "2") (pinfunction "2_2") (pintype "passive"))
      (node (ref "U1") (pin "7") (pinfunction "REGIN_7") (pintype "passive"))
      (node (ref "U1") (pin "8") (pinfunction "VBUS_8") (pintype "passive"))
      (node (ref "U4") (pin "4") (pinfunction "VCC_4") (pintype "passive"))
      (node (ref "USB1") (pin "A4") (pinfunction "VBUS_A4") (pintype "passive"))
      (node (ref "USB1") (pin "A9") (pinfunction "VBUS_A9") (pintype "passive"))
      (node (ref "USB1") (pin "B4") (pinfunction "VBUS_B4") (pintype "passive"))
      (node (ref "USB1") (pin "B9") (pinfunction "VBUS_B9") (pintype "passive"))
    )
    (net (code "61") (name "VCC_3V3") (class "Default")
      (node (ref "C1") (pin "2") (pinfunction "2_2") (pintype "passive"))
      (node (ref "C2") (pin "2") (pinfunction "2_2") (pintype "passive"))
      (node (ref "JP1") (pin "2") (pinfunction "2_2") (pintype "passive"))
      (node (ref "R8") (pin "1") (pinfunction "1_1") (pintype "passive"))
      (node (ref "UD1") (pin "3") (pinfunction "VOUT_3") (pintype "passive"))
      (node (ref "UV2") (pin "1") (pinfunction "VA+_1") (pintype "passive"))
    )
    (net (code "62") (name "VIN") (class "Default")
      (node (ref "CX1") (pin "1") (pinfunction "1_1") (pintype "passive"))
      (node (ref "R10") (pin "1") (pinfunction "1_1") (pintype "passive"))
      (node (ref "R11") (pin "1") (pinfunction "1_1") (pintype "passive"))
      (node (ref "UD1") (pin "2") (pinfunction "VIN_2") (pintype "passive"))
      (node (ref "UT1") (pin "2") (pinfunction "VIN_2") (pintype "passive"))
      (node (ref "UV1") (pin "5") (pinfunction "VIN_5") (pintype "passive"))
    )
    (net (code "63") (name "unconnected-(U1-*SUSPEND-Pad11)") (class "Default")
      (node (ref "U1") (pin "11") (pinfunction "*SUSPEND_11") (pintype "passive"))
    )
    (net (code "64") (name "unconnected-(U1-CTS-Pad23)") (class "Default")
      (node (ref "U1") (pin "23") (pinfunction "CTS_23") (pintype "passive"))
    )
    (net (code "65") (name "unconnected-(U1-DCD-Pad1)") (class "Default")
      (node (ref "U1") (pin "1") (pinfunction "DCD_1") (pintype "passive"))
    )
    (net (code "66") (name "unconnected-(U1-DSR-Pad27)") (class "Default")
      (node (ref "U1") (pin "27") (pinfunction "DSR_27") (pintype "passive"))
    )
    (net (code "67") (name "unconnected-(U1-NC-Pad10)") (class "Default")
      (node (ref "U1") (pin "10") (pinfunction "NC_10") (pintype "passive"))
    )
    (net (code "68") (name "unconnected-(U1-NC-Pad13)") (class "Default")
      (node (ref "U1") (pin "13") (pinfunction "NC_13") (pintype "passive"))
    )
    (net (code "69") (name "unconnected-(U1-NC-Pad14)") (class "Default")
      (node (ref "U1") (pin "14") (pinfunction "NC_14") (pintype "passive"))
    )
    (net (code "70") (name "unconnected-(U1-NC-Pad15)") (class "Default")
      (node (ref "U1") (pin "15") (pinfunction "NC_15") (pintype "passive"))
    )
    (net (code "71") (name "unconnected-(U1-NC-Pad16)") (class "Default")
      (node (ref "U1") (pin "16") (pinfunction "NC_16") (pintype "passive"))
    )
    (net (code "72") (name "unconnected-(U1-NC-Pad17)") (class "Default")
      (node (ref "U1") (pin "17") (pinfunction "NC_17") (pintype "passive"))
    )
    (net (code "73") (name "unconnected-(U1-NC-Pad18)") (class "Default")
      (node (ref "U1") (pin "18") (pinfunction "NC_18") (pintype "passive"))
    )
    (net (code "74") (name "unconnected-(U1-NC-Pad19)") (class "Default")
      (node (ref "U1") (pin "19") (pinfunction "NC_19") (pintype "passive"))
    )
    (net (code "75") (name "unconnected-(U1-NC-Pad20)") (class "Default")
      (node (ref "U1") (pin "20") (pinfunction "NC_20") (pintype "passive"))
    )
    (net (code "76") (name "unconnected-(U1-NC-Pad21)") (class "Default")
      (node (ref "U1") (pin "21") (pinfunction "NC_21") (pintype "passive"))
    )
    (net (code "77") (name "unconnected-(U1-NC-Pad22)") (class "Default")
      (node (ref "U1") (pin "22") (pinfunction "NC_22") (pintype "passive"))
    )
    (net (code "78") (name "unconnected-(U1-RI-Pad2)") (class "Default")
      (node (ref "U1") (pin "2") (pinfunction "RI_2") (pintype "passive"))
    )
    (net (code "79") (name "unconnected-(U1-SUSPEND-Pad12)") (class "Default")
      (node (ref "U1") (pin "12") (pinfunction "SUSPEND_12") (pintype "passive"))
    )
    (net (code "80") (name "unconnected-(U1-VDD-Pad6)") (class "Default")
      (node (ref "U1") (pin "6") (pinfunction "VDD_6") (pintype "passive"))
    )
    (net (code "81") (name "unconnected-(U3-VDD_RTC-Pad5)") (class "Default")
      (node (ref "U3") (pin "5") (pinfunction "VDD_RTC_5") (pintype "passive"))
    )
    (net (code "82") (name "unconnected-(U4-CHRG#-Pad1)") (class "Default")
      (node (ref "U4") (pin "1") (pinfunction "CHRG#_1") (pintype "passive"))
    )
    (net (code "83") (name "unconnected-(USB1-RX1+-PadB11)") (class "Default")
      (node (ref "USB1") (pin "B11") (pinfunction "RX1+_B11") (pintype "passive"))
    )
    (net (code "84") (name "unconnected-(USB1-RX1--PadB10)") (class "Default")
      (node (ref "USB1") (pin "B10") (pinfunction "RX1-_B10") (pintype "passive"))
    )
    (net (code "85") (name "unconnected-(USB1-RX2+-PadA11)") (class "Default")
      (node (ref "USB1") (pin "A11") (pinfunction "RX2+_A11") (pintype "passive"))
    )
    (net (code "86") (name "unconnected-(USB1-RX2--PadA10)") (class "Default")
      (node (ref "USB1") (pin "A10") (pinfunction "RX2-_A10") (pintype "passive"))
    )
    (net (code "87") (name "unconnected-(USB1-SBU1-PadA8)") (class "Default")
      (node (ref "USB1") (pin "A8") (pinfunction "SBU1_A8") (pintype "passive"))
    )
    (net (code "88") (name "unconnected-(USB1-SBU2-PadB8)") (class "Default")
      (node (ref "USB1") (pin "B8") (pinfunction "SBU2_B8") (pintype "passive"))
    )
    (net (code "89") (name "unconnected-(USB1-TX1+-PadA2)") (class "Default")
      (node (ref "USB1") (pin "A2") (pinfunction "TX1+_A2") (pintype "passive"))
    )
    (net (code "90") (name "unconnected-(USB1-TX1--PadA3)") (class "Default")
      (node (ref "USB1") (pin "A3") (pinfunction "TX1-_A3") (pintype "passive"))
    )
    (net (code "91") (name "unconnected-(USB1-TX2+-PadB2)") (class "Default")
      (node (ref "USB1") (pin "B2") (pinfunction "TX2+_B2") (pintype "passive"))
    )
    (net (code "92") (name "unconnected-(USB1-TX2--PadB3)") (class "Default")
      (node (ref "USB1") (pin "B3") (pinfunction "TX2-_B3") (pintype "passive"))
    )
    (net (code "93") (name "unconnected-(UV1-EN-Pad1)") (class "Default")
      (node (ref "UV1") (pin "1") (pinfunction "EN_1") (pintype "passive"))
    )
  )
)
